# Beta.net
KiCad netlist of a schematic drawn in EAGLE
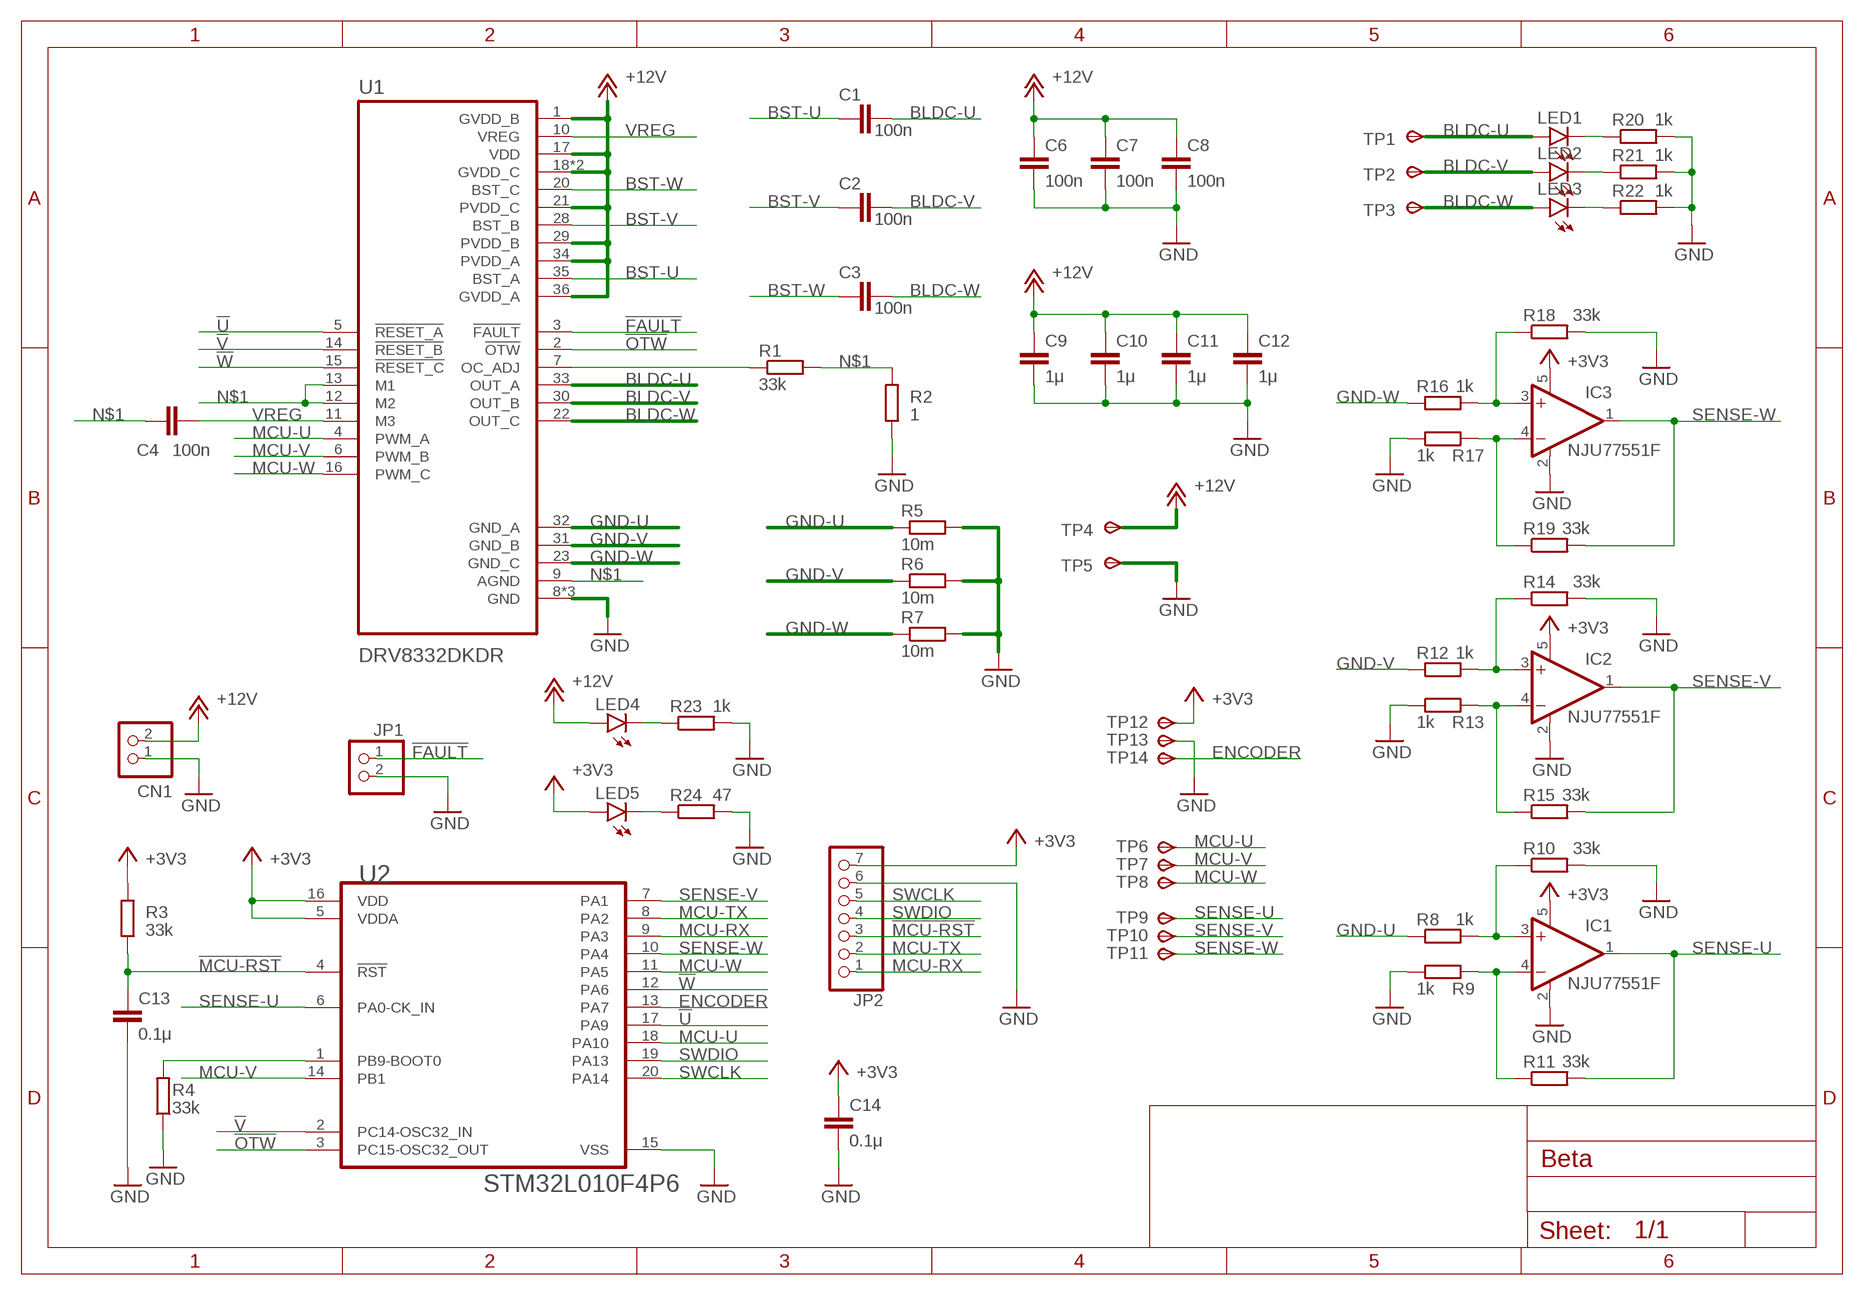
[diagram p0: schematic, sheet 1]

(export (version "E")
  (design (tool "Eeschema 10.0.6"))
  (components
    (comp (ref "C1")
      (value "100n")
      (footprint "eagle-import:C0603")
      (libsource (lib "eagle-import") (part "C-EUC0603"))
    )
    (comp (ref "C2")
      (value "100n")
      (footprint "eagle-import:C0603")
      (libsource (lib "eagle-import") (part "C-EUC0603"))
    )
    (comp (ref "C3")
      (value "100n")
      (footprint "eagle-import:C0603")
      (libsource (lib "eagle-import") (part "C-EUC0603"))
    )
    (comp (ref "C4")
      (value "100n")
      (footprint "eagle-import:C0603")
      (libsource (lib "eagle-import") (part "C-EUC0603"))
    )
    (comp (ref "C6")
      (value "100n")
      (footprint "eagle-import:C0603")
      (libsource (lib "eagle-import") (part "C-EUC0603"))
    )
    (comp (ref "C7")
      (value "100n")
      (footprint "eagle-import:C0603")
      (libsource (lib "eagle-import") (part "C-EUC0603"))
    )
    (comp (ref "C8")
      (value "100n")
      (footprint "eagle-import:C0603")
      (libsource (lib "eagle-import") (part "C-EUC0603"))
    )
    (comp (ref "C9")
      (value "1μ")
      (footprint "eagle-import:C0603")
      (libsource (lib "eagle-import") (part "C-EUC0603"))
    )
    (comp (ref "C10")
      (value "1μ")
      (footprint "eagle-import:C0603")
      (libsource (lib "eagle-import") (part "C-EUC0603"))
    )
    (comp (ref "C11")
      (value "1μ")
      (footprint "eagle-import:C0603")
      (libsource (lib "eagle-import") (part "C-EUC0603"))
    )
    (comp (ref "C12")
      (value "1μ")
      (footprint "eagle-import:C0603")
      (libsource (lib "eagle-import") (part "C-EUC0603"))
    )
    (comp (ref "C13")
      (value "0.1μ")
      (footprint "eagle-import:C0603")
      (libsource (lib "eagle-import") (part "C-EUC0603"))
    )
    (comp (ref "C14")
      (value "0.1μ")
      (footprint "eagle-import:C0603")
      (libsource (lib "eagle-import") (part "C-EUC0603"))
    )
    (comp (ref "CN1")
      (value "B2B-PH-K-S")
      (footprint "eagle-import:B2B-PH-K-S")
      (libsource (lib "eagle-import") (part "B2B-PH-K-S"))
    )
    (comp (ref "IC1")
      (value "NJU77551F")
      (footprint "eagle-import:SOT23-5")
      (fields (field (name "MPN") "OPA340NA/3KG4"))
      (libsource (lib "eagle-import") (part "OPA340N"))
    )
    (comp (ref "IC2")
      (value "NJU77551F")
      (footprint "eagle-import:SOT23-5")
      (fields (field (name "MPN") "OPA340NA/3KG4"))
      (libsource (lib "eagle-import") (part "OPA340N"))
    )
    (comp (ref "IC3")
      (value "NJU77551F")
      (footprint "eagle-import:SOT23-5")
      (fields (field (name "MPN") "OPA340NA/3KG4"))
      (libsource (lib "eagle-import") (part "OPA340N"))
    )
    (comp (ref "JP1")
      (value "PINHD-1X2/90")
      (footprint "eagle-import:1X02_90")
      (libsource (lib "eagle-import") (part "PINHD-1X2/90"))
    )
    (comp (ref "JP2")
      (value "PINHD-1X7/90")
      (footprint "eagle-import:1X07_90")
      (libsource (lib "eagle-import") (part "PINHD-1X7/90"))
    )
    (comp (ref "LED1")
      (value "LEDCHIPLED_0603")
      (footprint "eagle-import:CHIPLED_0603")
      (libsource (lib "eagle-import") (part "LEDCHIPLED_0603"))
    )
    (comp (ref "LED2")
      (value "LEDCHIPLED_0603")
      (footprint "eagle-import:CHIPLED_0603")
      (libsource (lib "eagle-import") (part "LEDCHIPLED_0603"))
    )
    (comp (ref "LED3")
      (value "LEDCHIPLED_0603")
      (footprint "eagle-import:CHIPLED_0603")
      (libsource (lib "eagle-import") (part "LEDCHIPLED_0603"))
    )
    (comp (ref "LED4")
      (value "LEDCHIPLED_0603")
      (footprint "eagle-import:CHIPLED_0603")
      (libsource (lib "eagle-import") (part "LEDCHIPLED_0603"))
    )
    (comp (ref "LED5")
      (value "LEDCHIPLED_0603")
      (footprint "eagle-import:CHIPLED_0603")
      (libsource (lib "eagle-import") (part "LEDCHIPLED_0603"))
    )
    (comp (ref "R1")
      (value "33k")
      (footprint "eagle-import:R0603")
      (libsource (lib "eagle-import") (part "R-EU_R0603"))
    )
    (comp (ref "R2")
      (value "1")
      (footprint "eagle-import:R0603")
      (libsource (lib "eagle-import") (part "R-EU_R0603"))
    )
    (comp (ref "R3")
      (value "33k")
      (footprint "eagle-import:R0603")
      (libsource (lib "eagle-import") (part "R-EU_R0603"))
    )
    (comp (ref "R4")
      (value "33k")
      (footprint "eagle-import:R0603")
      (libsource (lib "eagle-import") (part "R-EU_R0603"))
    )
    (comp (ref "R5")
      (value "10m")
      (footprint "eagle-import:R3216")
      (libsource (lib "eagle-import") (part "R-EU_R3216"))
    )
    (comp (ref "R6")
      (value "10m")
      (footprint "eagle-import:R3216")
      (libsource (lib "eagle-import") (part "R-EU_R3216"))
    )
    (comp (ref "R7")
      (value "10m")
      (footprint "eagle-import:R3216")
      (libsource (lib "eagle-import") (part "R-EU_R3216"))
    )
    (comp (ref "R8")
      (value "1k")
      (footprint "eagle-import:R0603")
      (libsource (lib "eagle-import") (part "R-EU_R0603"))
    )
    (comp (ref "R9")
      (value "1k")
      (footprint "eagle-import:R0603")
      (libsource (lib "eagle-import") (part "R-EU_R0603"))
    )
    (comp (ref "R10")
      (value "33k")
      (footprint "eagle-import:R0603")
      (libsource (lib "eagle-import") (part "R-EU_R0603"))
    )
    (comp (ref "R11")
      (value "33k")
      (footprint "eagle-import:R0603")
      (libsource (lib "eagle-import") (part "R-EU_R0603"))
    )
    (comp (ref "R12")
      (value "1k")
      (footprint "eagle-import:R0603")
      (libsource (lib "eagle-import") (part "R-EU_R0603"))
    )
    (comp (ref "R13")
      (value "1k")
      (footprint "eagle-import:R0603")
      (libsource (lib "eagle-import") (part "R-EU_R0603"))
    )
    (comp (ref "R14")
      (value "33k")
      (footprint "eagle-import:R0603")
      (libsource (lib "eagle-import") (part "R-EU_R0603"))
    )
    (comp (ref "R15")
      (value "33k")
      (footprint "eagle-import:R0603")
      (libsource (lib "eagle-import") (part "R-EU_R0603"))
    )
    (comp (ref "R16")
      (value "1k")
      (footprint "eagle-import:R0603")
      (libsource (lib "eagle-import") (part "R-EU_R0603"))
    )
    (comp (ref "R17")
      (value "1k")
      (footprint "eagle-import:R0603")
      (libsource (lib "eagle-import") (part "R-EU_R0603"))
    )
    (comp (ref "R18")
      (value "33k")
      (footprint "eagle-import:R0603")
      (libsource (lib "eagle-import") (part "R-EU_R0603"))
    )
    (comp (ref "R19")
      (value "33k")
      (footprint "eagle-import:R0603")
      (libsource (lib "eagle-import") (part "R-EU_R0603"))
    )
    (comp (ref "R20")
      (value "1k")
      (footprint "eagle-import:R0603")
      (libsource (lib "eagle-import") (part "R-EU_R0603"))
    )
    (comp (ref "R21")
      (value "1k")
      (footprint "eagle-import:R0603")
      (libsource (lib "eagle-import") (part "R-EU_R0603"))
    )
    (comp (ref "R22")
      (value "1k")
      (footprint "eagle-import:R0603")
      (libsource (lib "eagle-import") (part "R-EU_R0603"))
    )
    (comp (ref "R23")
      (value "1k")
      (footprint "eagle-import:R0603")
      (libsource (lib "eagle-import") (part "R-EU_R0603"))
    )
    (comp (ref "R24")
      (value "47")
      (footprint "eagle-import:R0603")
      (libsource (lib "eagle-import") (part "R-EU_R0603"))
    )
    (comp (ref "TP1")
      (value "TPSPAD1-20")
      (footprint "eagle-import:P1-20")
      (libsource (lib "eagle-import") (part "TPSPAD1-20"))
    )
    (comp (ref "TP2")
      (value "TPSPAD1-20")
      (footprint "eagle-import:P1-20")
      (libsource (lib "eagle-import") (part "TPSPAD1-20"))
    )
    (comp (ref "TP3")
      (value "TPSPAD1-20")
      (footprint "eagle-import:P1-20")
      (libsource (lib "eagle-import") (part "TPSPAD1-20"))
    )
    (comp (ref "TP4")
      (value "TPSPAD1-20")
      (footprint "eagle-import:P1-20")
      (libsource (lib "eagle-import") (part "TPSPAD1-20"))
    )
    (comp (ref "TP5")
      (value "TPSPAD1-20")
      (footprint "eagle-import:P1-20")
      (libsource (lib "eagle-import") (part "TPSPAD1-20"))
    )
    (comp (ref "TP6")
      (value "TPSTP11SQ")
      (footprint "eagle-import:TP11SQ")
      (libsource (lib "eagle-import") (part "TPSTP11SQ"))
    )
    (comp (ref "TP7")
      (value "TPSTP11R")
      (footprint "eagle-import:TP11R")
      (libsource (lib "eagle-import") (part "TPSTP11R"))
    )
    (comp (ref "TP8")
      (value "TPSTP11R")
      (footprint "eagle-import:TP11R")
      (libsource (lib "eagle-import") (part "TPSTP11R"))
    )
    (comp (ref "TP9")
      (value "TPSTP11SQ")
      (footprint "eagle-import:TP11SQ")
      (libsource (lib "eagle-import") (part "TPSTP11SQ"))
    )
    (comp (ref "TP10")
      (value "TPSTP11R")
      (footprint "eagle-import:TP11R")
      (libsource (lib "eagle-import") (part "TPSTP11R"))
    )
    (comp (ref "TP11")
      (value "TPSTP11R")
      (footprint "eagle-import:TP11R")
      (libsource (lib "eagle-import") (part "TPSTP11R"))
    )
    (comp (ref "TP12")
      (value "TPSTP11SQ")
      (footprint "eagle-import:TP11SQ")
      (libsource (lib "eagle-import") (part "TPSTP11SQ"))
    )
    (comp (ref "TP13")
      (value "TPSTP11R")
      (footprint "eagle-import:TP11R")
      (libsource (lib "eagle-import") (part "TPSTP11R"))
    )
    (comp (ref "TP14")
      (value "TPSTP11R")
      (footprint "eagle-import:TP11R")
      (libsource (lib "eagle-import") (part "TPSTP11R"))
    )
    (comp (ref "U1")
      (value "DRV8332DKDR")
      (footprint "eagle-import:SOP65P1420X360-36N")
      (fields (field (name "DIGI-KEY_PART_NUMBER") "296-29572-1-ND") (field (name "MF") "Texas Instruments"))
      (libsource (lib "eagle-import") (part "DRV8332DKDR"))
    )
    (comp (ref "U2")
      (value "STMICROELECTRONICS_STM32L010F4P6STMICROELECTRONICS_STM32L010F4P6_0_2")
      (footprint "eagle-import:STMICROELECTRONICS_STM32L010F4P6_2")
      (fields
        (field (name "DIGIKEY_PART_NUMBER") "497-19364-ND")
        (field (name "MF") "STMicroelectronics")
        (field (name "MOUSER_PART_NUMBER") "511-STM32L010F4P6")
      )
      (libsource (lib "eagle-import") (part "STMICROELECTRONICS_STM32L010F4P6STMICROELECTRONICS_STM32L010F4P6_0_2"))
    )
  )
  (nets
    (net (code "1") (name "+3V3") (class "Default")
      (node (ref "C14") (pin "1") (pinfunction "1_1") (pintype "passive"))
      (node (ref "IC1") (pin "5") (pinfunction "V+_5") (pintype "power_in"))
      (node (ref "IC2") (pin "5") (pinfunction "V+_5") (pintype "power_in"))
      (node (ref "IC3") (pin "5") (pinfunction "V+_5") (pintype "power_in"))
      (node (ref "JP2") (pin "7") (pinfunction "7_7") (pintype "passive"))
      (node (ref "LED5") (pin "A") (pinfunction "A_A") (pintype "passive"))
      (node (ref "R3") (pin "2") (pinfunction "2_2") (pintype "passive"))
      (node (ref "TP12") (pin "TP") (pinfunction "PP_TP") (pintype "input"))
      (node (ref "U2") (pin "16") (pinfunction "VDD_16") (pintype "power_in"))
      (node (ref "U2") (pin "5") (pinfunction "VDDA_5") (pintype "power_in"))
    )
    (net (code "2") (name "+12V") (class "Default")
      (node (ref "C10") (pin "1") (pinfunction "1_1") (pintype "passive"))
      (node (ref "C11") (pin "1") (pinfunction "1_1") (pintype "passive"))
      (node (ref "C12") (pin "1") (pinfunction "1_1") (pintype "passive"))
      (node (ref "C6") (pin "1") (pinfunction "1_1") (pintype "passive"))
      (node (ref "C7") (pin "1") (pinfunction "1_1") (pintype "passive"))
      (node (ref "C8") (pin "1") (pinfunction "1_1") (pintype "passive"))
      (node (ref "C9") (pin "1") (pinfunction "1_1") (pintype "passive"))
      (node (ref "CN1") (pin "2") (pinfunction "2_2") (pintype "passive"))
      (node (ref "LED4") (pin "A") (pinfunction "A_A") (pintype "passive"))
      (node (ref "TP4") (pin "TP") (pinfunction "PP_TP") (pintype "input"))
      (node (ref "U1") (pin "1") (pinfunction "GVDD_B_1") (pintype "power_in"))
      (node (ref "U1") (pin "17") (pinfunction "VDD_17") (pintype "power_in"))
      (node (ref "U1") (pin "18") (pinfunction "GVDD_C_18") (pintype "power_in"))
      (node (ref "U1") (pin "19") (pinfunction "GVDD_C_19") (pintype "power_in"))
      (node (ref "U1") (pin "21") (pinfunction "PVDD_C_21") (pintype "power_in"))
      (node (ref "U1") (pin "29") (pinfunction "PVDD_B_29") (pintype "power_in"))
      (node (ref "U1") (pin "34") (pinfunction "PVDD_A_34") (pintype "power_in"))
      (node (ref "U1") (pin "36") (pinfunction "GVDD_A_36") (pintype "power_in"))
    )
    (net (code "3") (name "/BLDC-U") (class "Default")
      (node (ref "C1") (pin "1") (pinfunction "1_1") (pintype "passive"))
      (node (ref "LED1") (pin "A") (pinfunction "A_A") (pintype "passive"))
      (node (ref "TP1") (pin "TP") (pinfunction "PP_TP") (pintype "input"))
      (node (ref "U1") (pin "33") (pinfunction "OUT_A_33") (pintype "output"))
    )
    (net (code "4") (name "/BLDC-V") (class "Default")
      (node (ref "C2") (pin "1") (pinfunction "1_1") (pintype "passive"))
      (node (ref "LED2") (pin "A") (pinfunction "A_A") (pintype "passive"))
      (node (ref "TP2") (pin "TP") (pinfunction "PP_TP") (pintype "input"))
      (node (ref "U1") (pin "30") (pinfunction "OUT_B_30") (pintype "output"))
    )
    (net (code "5") (name "/BLDC-W") (class "Default")
      (node (ref "C3") (pin "1") (pinfunction "1_1") (pintype "passive"))
      (node (ref "LED3") (pin "A") (pinfunction "A_A") (pintype "passive"))
      (node (ref "TP3") (pin "TP") (pinfunction "PP_TP") (pintype "input"))
      (node (ref "U1") (pin "22") (pinfunction "OUT_C_22") (pintype "output"))
    )
    (net (code "6") (name "/BST-U") (class "Default")
      (node (ref "C1") (pin "2") (pinfunction "2_2") (pintype "passive"))
      (node (ref "U1") (pin "35") (pinfunction "BST_A_35") (pintype "power_in"))
    )
    (net (code "7") (name "/BST-V") (class "Default")
      (node (ref "C2") (pin "2") (pinfunction "2_2") (pintype "passive"))
      (node (ref "U1") (pin "28") (pinfunction "BST_B_28") (pintype "power_in"))
    )
    (net (code "8") (name "/BST-W") (class "Default")
      (node (ref "C3") (pin "2") (pinfunction "2_2") (pintype "passive"))
      (node (ref "U1") (pin "20") (pinfunction "BST_C_20") (pintype "power_in"))
    )
    (net (code "9") (name "/ENCODER") (class "Default")
      (node (ref "TP14") (pin "TP") (pinfunction "PP_TP") (pintype "input"))
      (node (ref "U2") (pin "13") (pinfunction "PA7_13") (pintype "bidirectional"))
    )
    (net (code "10") (name "/GND-U") (class "Default")
      (node (ref "R5") (pin "1") (pinfunction "1_1") (pintype "passive"))
      (node (ref "R8") (pin "1") (pinfunction "1_1") (pintype "passive"))
      (node (ref "U1") (pin "32") (pinfunction "GND_A_32") (pintype "power_in"))
    )
    (net (code "11") (name "/GND-V") (class "Default")
      (node (ref "R12") (pin "1") (pinfunction "1_1") (pintype "passive"))
      (node (ref "R6") (pin "1") (pinfunction "1_1") (pintype "passive"))
      (node (ref "U1") (pin "31") (pinfunction "GND_B_31") (pintype "power_in"))
    )
    (net (code "12") (name "/GND-W") (class "Default")
      (node (ref "R16") (pin "1") (pinfunction "1_1") (pintype "passive"))
      (node (ref "R7") (pin "1") (pinfunction "1_1") (pintype "passive"))
      (node (ref "U1") (pin "23") (pinfunction "GND_C_23") (pintype "power_in"))
    )
    (net (code "13") (name "/MCU-RX") (class "Default")
      (node (ref "JP2") (pin "1") (pinfunction "1_1") (pintype "passive"))
      (node (ref "U2") (pin "9") (pinfunction "PA3_9") (pintype "bidirectional"))
    )
    (net (code "14") (name "/MCU-TX") (class "Default")
      (node (ref "JP2") (pin "2") (pinfunction "2_2") (pintype "passive"))
      (node (ref "U2") (pin "8") (pinfunction "PA2_8") (pintype "bidirectional"))
    )
    (net (code "15") (name "/MCU-U") (class "Default")
      (node (ref "TP6") (pin "TP") (pinfunction "PP_TP") (pintype "input"))
      (node (ref "U1") (pin "4") (pinfunction "PWM_A_4") (pintype "input"))
      (node (ref "U2") (pin "18") (pinfunction "PA10_18") (pintype "bidirectional"))
    )
    (net (code "16") (name "/MCU-V") (class "Default")
      (node (ref "TP7") (pin "TP") (pinfunction "PP_TP") (pintype "input"))
      (node (ref "U1") (pin "6") (pinfunction "PWM_B_6") (pintype "input"))
      (node (ref "U2") (pin "14") (pinfunction "PB1_14") (pintype "bidirectional"))
    )
    (net (code "17") (name "/MCU-W") (class "Default")
      (node (ref "TP8") (pin "TP") (pinfunction "PP_TP") (pintype "input"))
      (node (ref "U1") (pin "16") (pinfunction "PWM_C_16") (pintype "input"))
      (node (ref "U2") (pin "11") (pinfunction "PA5_11") (pintype "bidirectional"))
    )
    (net (code "18") (name "/N$1") (class "Default")
      (node (ref "C4") (pin "1") (pinfunction "1_1") (pintype "passive"))
      (node (ref "R1") (pin "2") (pinfunction "2_2") (pintype "passive"))
      (node (ref "R2") (pin "2") (pinfunction "2_2") (pintype "passive"))
      (node (ref "U1") (pin "12") (pinfunction "M2_12") (pintype "input"))
      (node (ref "U1") (pin "13") (pinfunction "M1_13") (pintype "input"))
      (node (ref "U1") (pin "9") (pinfunction "AGND_9") (pintype "power_in"))
    )
    (net (code "19") (name "/SENSE-U") (class "Default")
      (node (ref "IC1") (pin "1") (pinfunction "OUT_1") (pintype "output"))
      (node (ref "R11") (pin "2") (pinfunction "2_2") (pintype "passive"))
      (node (ref "TP9") (pin "TP") (pinfunction "PP_TP") (pintype "input"))
      (node (ref "U2") (pin "6") (pinfunction "PA0-CK_IN_6") (pintype "bidirectional"))
    )
    (net (code "20") (name "/SENSE-V") (class "Default")
      (node (ref "IC2") (pin "1") (pinfunction "OUT_1") (pintype "output"))
      (node (ref "R15") (pin "2") (pinfunction "2_2") (pintype "passive"))
      (node (ref "TP10") (pin "TP") (pinfunction "PP_TP") (pintype "input"))
      (node (ref "U2") (pin "7") (pinfunction "PA1_7") (pintype "bidirectional"))
    )
    (net (code "21") (name "/SENSE-W") (class "Default")
      (node (ref "IC3") (pin "1") (pinfunction "OUT_1") (pintype "output"))
      (node (ref "R19") (pin "2") (pinfunction "2_2") (pintype "passive"))
      (node (ref "TP11") (pin "TP") (pinfunction "PP_TP") (pintype "input"))
      (node (ref "U2") (pin "10") (pinfunction "PA4_10") (pintype "bidirectional"))
    )
    (net (code "22") (name "/SWCLK") (class "Default")
      (node (ref "JP2") (pin "5") (pinfunction "5_5") (pintype "passive"))
      (node (ref "U2") (pin "20") (pinfunction "PA14_20") (pintype "bidirectional"))
    )
    (net (code "23") (name "/SWDIO") (class "Default")
      (node (ref "JP2") (pin "4") (pinfunction "4_4") (pintype "passive"))
      (node (ref "U2") (pin "19") (pinfunction "PA13_19") (pintype "bidirectional"))
    )
    (net (code "24") (name "/VREG") (class "Default")
      (node (ref "C4") (pin "2") (pinfunction "2_2") (pintype "passive"))
      (node (ref "U1") (pin "10") (pinfunction "VREG_10") (pintype "power_in"))
      (node (ref "U1") (pin "11") (pinfunction "M3_11") (pintype "input"))
    )
    (net (code "25") (name "/~{FAULT}") (class "Default")
      (node (ref "JP1") (pin "1") (pinfunction "1_1") (pintype "passive"))
      (node (ref "U1") (pin "3") (pinfunction "~{FAULT}_3") (pintype "output"))
    )
    (net (code "26") (name "/~{MCU-RST}") (class "Default")
      (node (ref "C13") (pin "1") (pinfunction "1_1") (pintype "passive"))
      (node (ref "JP2") (pin "3") (pinfunction "3_3") (pintype "passive"))
      (node (ref "R3") (pin "1") (pinfunction "1_1") (pintype "passive"))
      (node (ref "U2") (pin "4") (pinfunction "~{RST}_4") (pintype "input"))
    )
    (net (code "27") (name "/~{OTW}") (class "Default")
      (node (ref "U1") (pin "2") (pinfunction "~{OTW}_2") (pintype "output"))
      (node (ref "U2") (pin "3") (pinfunction "PC15-OSC32_OUT_3") (pintype "bidirectional"))
    )
    (net (code "28") (name "/~{U}") (class "Default")
      (node (ref "U1") (pin "5") (pinfunction "~{RESET_A}_5") (pintype "input"))
      (node (ref "U2") (pin "17") (pinfunction "PA9_17") (pintype "bidirectional"))
    )
    (net (code "29") (name "/~{V}") (class "Default")
      (node (ref "U1") (pin "14") (pinfunction "~{RESET_B}_14") (pintype "input"))
      (node (ref "U2") (pin "2") (pinfunction "PC14-OSC32_IN_2") (pintype "bidirectional"))
    )
    (net (code "30") (name "/~{W}") (class "Default")
      (node (ref "U1") (pin "15") (pinfunction "~{RESET_C}_15") (pintype "input"))
      (node (ref "U2") (pin "12") (pinfunction "PA6_12") (pintype "bidirectional"))
    )
    (net (code "31") (name "GND") (class "Default")
      (node (ref "C10") (pin "2") (pinfunction "2_2") (pintype "passive"))
      (node (ref "C11") (pin "2") (pinfunction "2_2") (pintype "passive"))
      (node (ref "C12") (pin "2") (pinfunction "2_2") (pintype "passive"))
      (node (ref "C13") (pin "2") (pinfunction "2_2") (pintype "passive"))
      (node (ref "C14") (pin "2") (pinfunction "2_2") (pintype "passive"))
      (node (ref "C6") (pin "2") (pinfunction "2_2") (pintype "passive"))
      (node (ref "C7") (pin "2") (pinfunction "2_2") (pintype "passive"))
      (node (ref "C8") (pin "2") (pinfunction "2_2") (pintype "passive"))
      (node (ref "C9") (pin "2") (pinfunction "2_2") (pintype "passive"))
      (node (ref "CN1") (pin "1") (pinfunction "1_1") (pintype "passive"))
      (node (ref "IC1") (pin "2") (pinfunction "V-_2") (pintype "power_in"))
      (node (ref "IC2") (pin "2") (pinfunction "V-_2") (pintype "power_in"))
      (node (ref "IC3") (pin "2") (pinfunction "V-_2") (pintype "power_in"))
      (node (ref "JP1") (pin "2") (pinfunction "2_2") (pintype "passive"))
      (node (ref "JP2") (pin "6") (pinfunction "6_6") (pintype "passive"))
      (node (ref "R10") (pin "2") (pinfunction "2_2") (pintype "passive"))
      (node (ref "R13") (pin "1") (pinfunction "1_1") (pintype "passive"))
      (node (ref "R14") (pin "2") (pinfunction "2_2") (pintype "passive"))
      (node (ref "R17") (pin "1") (pinfunction "1_1") (pintype "passive"))
      (node (ref "R18") (pin "2") (pinfunction "2_2") (pintype "passive"))
      (node (ref "R2") (pin "1") (pinfunction "1_1") (pintype "passive"))
      (node (ref "R20") (pin "2") (pinfunction "2_2") (pintype "passive"))
      (node (ref "R21") (pin "2") (pinfunction "2_2") (pintype "passive"))
      (node (ref "R22") (pin "2") (pinfunction "2_2") (pintype "passive"))
      (node (ref "R23") (pin "2") (pinfunction "2_2") (pintype "passive"))
      (node (ref "R24") (pin "2") (pinfunction "2_2") (pintype "passive"))
      (node (ref "R4") (pin "1") (pinfunction "1_1") (pintype "passive"))
      (node (ref "R5") (pin "2") (pinfunction "2_2") (pintype "passive"))
      (node (ref "R6") (pin "2") (pinfunction "2_2") (pintype "passive"))
      (node (ref "R7") (pin "2") (pinfunction "2_2") (pintype "passive"))
      (node (ref "R9") (pin "1") (pinfunction "1_1") (pintype "passive"))
      (node (ref "TP13") (pin "TP") (pinfunction "PP_TP") (pintype "input"))
      (node (ref "TP5") (pin "TP") (pinfunction "PP_TP") (pintype "input"))
      (node (ref "U1") (pin "24") (pinfunction "GND_24") (pintype "power_in"))
      (node (ref "U1") (pin "25") (pinfunction "GND_25") (pintype "power_in"))
      (node (ref "U1") (pin "8") (pinfunction "GND_8") (pintype "power_in"))
      (node (ref "U2") (pin "15") (pinfunction "VSS_15") (pintype "power_in"))
    )
    (net (code "32") (name "Net-(IC1-+IN)") (class "Default")
      (node (ref "IC1") (pin "3") (pinfunction "+IN_3") (pintype "input"))
      (node (ref "R10") (pin "1") (pinfunction "1_1") (pintype "passive"))
      (node (ref "R8") (pin "2") (pinfunction "2_2") (pintype "passive"))
    )
    (net (code "33") (name "Net-(IC1--IN)") (class "Default")
      (node (ref "IC1") (pin "4") (pinfunction "-IN_4") (pintype "input"))
      (node (ref "R11") (pin "1") (pinfunction "1_1") (pintype "passive"))
      (node (ref "R9") (pin "2") (pinfunction "2_2") (pintype "passive"))
    )
    (net (code "34") (name "Net-(IC2-+IN)") (class "Default")
      (node (ref "IC2") (pin "3") (pinfunction "+IN_3") (pintype "input"))
      (node (ref "R12") (pin "2") (pinfunction "2_2") (pintype "passive"))
      (node (ref "R14") (pin "1") (pinfunction "1_1") (pintype "passive"))
    )
    (net (code "35") (name "Net-(IC2--IN)") (class "Default")
      (node (ref "IC2") (pin "4") (pinfunction "-IN_4") (pintype "input"))
      (node (ref "R13") (pin "2") (pinfunction "2_2") (pintype "passive"))
      (node (ref "R15") (pin "1") (pinfunction "1_1") (pintype "passive"))
    )
    (net (code "36") (name "Net-(IC3-+IN)") (class "Default")
      (node (ref "IC3") (pin "3") (pinfunction "+IN_3") (pintype "input"))
      (node (ref "R16") (pin "2") (pinfunction "2_2") (pintype "passive"))
      (node (ref "R18") (pin "1") (pinfunction "1_1") (pintype "passive"))
    )
    (net (code "37") (name "Net-(IC3--IN)") (class "Default")
      (node (ref "IC3") (pin "4") (pinfunction "-IN_4") (pintype "input"))
      (node (ref "R17") (pin "2") (pinfunction "2_2") (pintype "passive"))
      (node (ref "R19") (pin "1") (pinfunction "1_1") (pintype "passive"))
    )
    (net (code "38") (name "Net-(LED1-PadC)") (class "Default")
      (node (ref "LED1") (pin "C") (pinfunction "C_C") (pintype "passive"))
      (node (ref "R20") (pin "1") (pinfunction "1_1") (pintype "passive"))
    )
    (net (code "39") (name "Net-(LED2-PadC)") (class "Default")
      (node (ref "LED2") (pin "C") (pinfunction "C_C") (pintype "passive"))
      (node (ref "R21") (pin "1") (pinfunction "1_1") (pintype "passive"))
    )
    (net (code "40") (name "Net-(LED3-PadC)") (class "Default")
      (node (ref "LED3") (pin "C") (pinfunction "C_C") (pintype "passive"))
      (node (ref "R22") (pin "1") (pinfunction "1_1") (pintype "passive"))
    )
    (net (code "41") (name "Net-(LED4-PadC)") (class "Default")
      (node (ref "LED4") (pin "C") (pinfunction "C_C") (pintype "passive"))
      (node (ref "R23") (pin "1") (pinfunction "1_1") (pintype "passive"))
    )
    (net (code "42") (name "Net-(LED5-PadC)") (class "Default")
      (node (ref "LED5") (pin "C") (pinfunction "C_C") (pintype "passive"))
      (node (ref "R24") (pin "1") (pinfunction "1_1") (pintype "passive"))
    )
    (net (code "43") (name "Net-(U1-OC_ADJ)") (class "Default")
      (node (ref "R1") (pin "1") (pinfunction "1_1") (pintype "passive"))
      (node (ref "U1") (pin "7") (pinfunction "OC_ADJ_7") (pintype "output"))
    )
    (net (code "44") (name "Net-(U2-PB9-BOOT0)") (class "Default")
      (node (ref "R4") (pin "2") (pinfunction "2_2") (pintype "passive"))
      (node (ref "U2") (pin "1") (pinfunction "PB9-BOOT0_1") (pintype "input"))
    )
  )
)
